# testBench.net
KiCad netlist of a schematic drawn in EAGLE
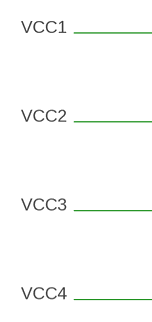
[diagram p0: schematic, sheet 1, part 1 of 2]
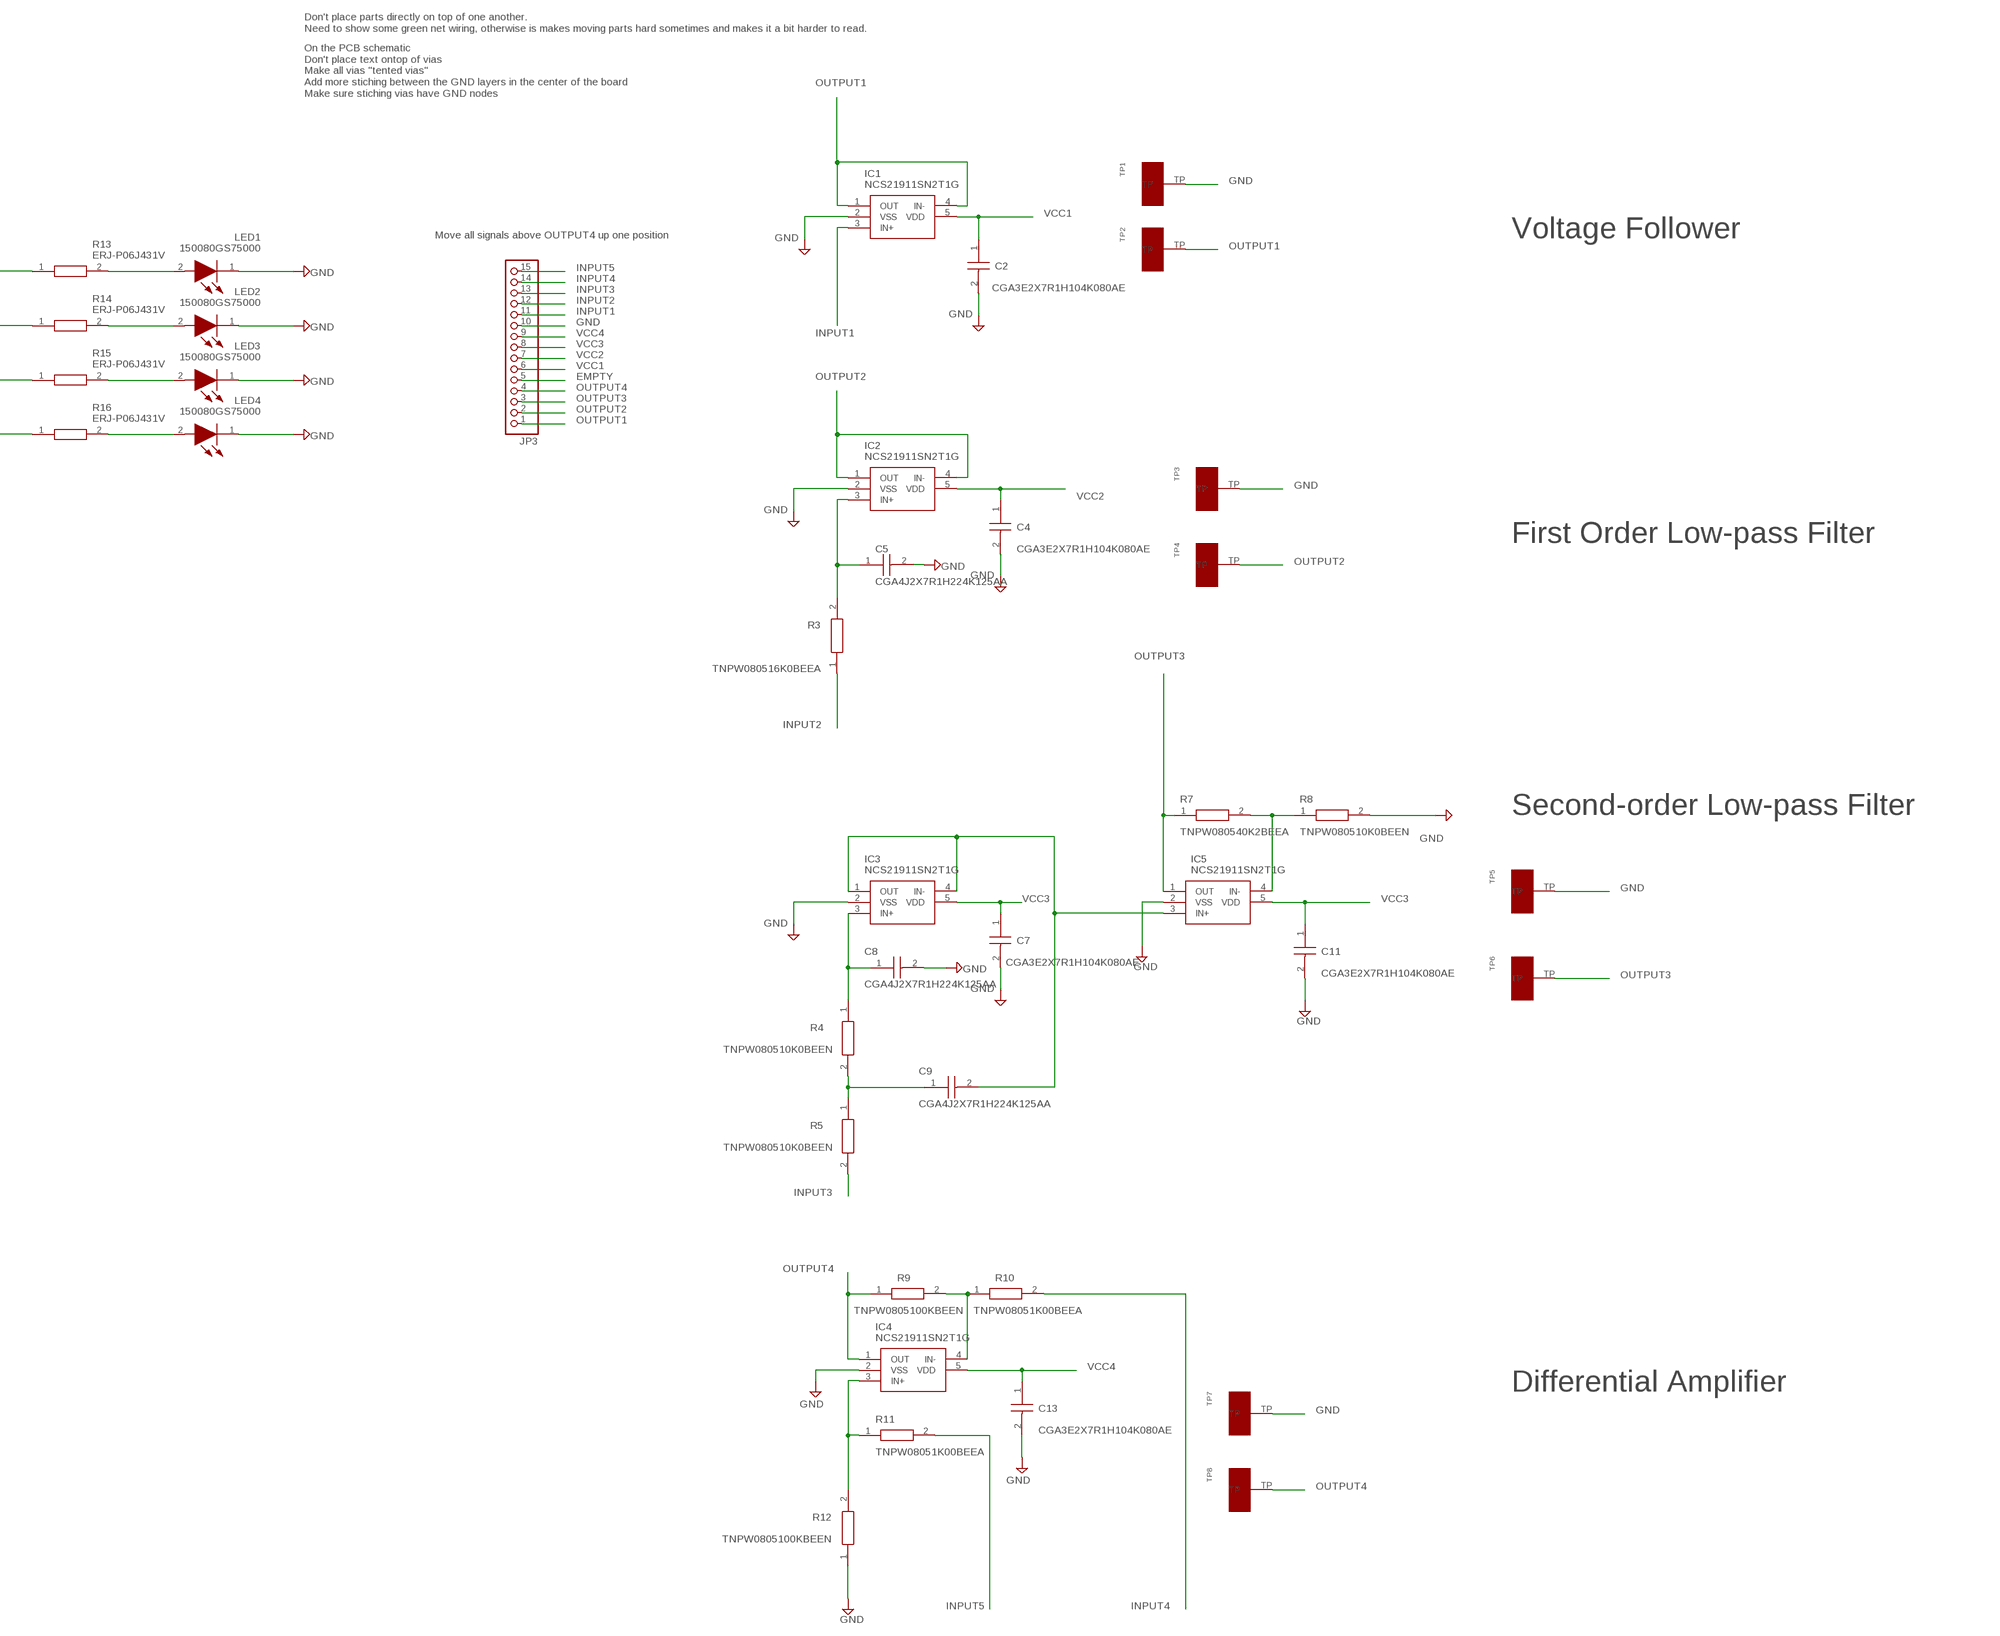
[diagram p1: schematic, sheet 1, part 2 of 2]

(export (version "E")
  (design (tool "Eeschema 10.0.6"))
  (components
    (comp (ref "C2")
      (value "CGA3E2X7R1H104K080AE")
      (footprint "eagle-import:CAPC1608X90N")
      (fields (field (name "MOUSER_PART_NUMBER") "810-CGA3E2X7R1H104KE"))
      (libsource (lib "eagle-import") (part "CGA3E2X7R1H104K080AE"))
    )
    (comp (ref "C4")
      (value "CGA3E2X7R1H104K080AE")
      (footprint "eagle-import:CAPC1608X90N")
      (fields (field (name "MOUSER_PART_NUMBER") "810-CGA3E2X7R1H104KE"))
      (libsource (lib "eagle-import") (part "CGA3E2X7R1H104K080AE"))
    )
    (comp (ref "C5")
      (value "CGA4J2X7R1H224K125AA")
      (footprint "eagle-import:CAPC2012X145N")
      (fields (field (name "MOUSER_PART_NUMBER") "810-CGA4J2X7R1H224K"))
      (libsource (lib "eagle-import") (part "CGA4J2X7R1H224K125AA"))
    )
    (comp (ref "C7")
      (value "CGA3E2X7R1H104K080AE")
      (footprint "eagle-import:CAPC1608X90N")
      (fields (field (name "MOUSER_PART_NUMBER") "810-CGA3E2X7R1H104KE"))
      (libsource (lib "eagle-import") (part "CGA3E2X7R1H104K080AE"))
    )
    (comp (ref "C8")
      (value "CGA4J2X7R1H224K125AA")
      (footprint "eagle-import:CAPC2012X145N")
      (fields (field (name "MOUSER_PART_NUMBER") "810-CGA4J2X7R1H224K"))
      (libsource (lib "eagle-import") (part "CGA4J2X7R1H224K125AA"))
    )
    (comp (ref "C9")
      (value "CGA4J2X7R1H224K125AA")
      (footprint "eagle-import:CAPC2012X145N")
      (fields (field (name "MOUSER_PART_NUMBER") "810-CGA4J2X7R1H224K"))
      (libsource (lib "eagle-import") (part "CGA4J2X7R1H224K125AA"))
    )
    (comp (ref "C11")
      (value "CGA3E2X7R1H104K080AE")
      (footprint "eagle-import:CAPC1608X90N")
      (fields (field (name "MOUSER_PART_NUMBER") "810-CGA3E2X7R1H104KE"))
      (libsource (lib "eagle-import") (part "CGA3E2X7R1H104K080AE"))
    )
    (comp (ref "C13")
      (value "CGA3E2X7R1H104K080AE")
      (footprint "eagle-import:CAPC1608X90N")
      (fields (field (name "MOUSER_PART_NUMBER") "810-CGA3E2X7R1H104KE"))
      (libsource (lib "eagle-import") (part "CGA3E2X7R1H104K080AE"))
    )
    (comp (ref "IC1")
      (value "NCS21911SN2T1G")
      (footprint "eagle-import:SOT95P275X110-5N")
      (fields (field (name "MOUSER_PART_NUMBER") "863-NCS21911SN2T1G"))
      (libsource (lib "eagle-import") (part "NCS21911SN2T1G"))
    )
    (comp (ref "IC2")
      (value "NCS21911SN2T1G")
      (footprint "eagle-import:SOT95P275X110-5N")
      (fields (field (name "MOUSER_PART_NUMBER") "863-NCS21911SN2T1G"))
      (libsource (lib "eagle-import") (part "NCS21911SN2T1G"))
    )
    (comp (ref "IC3")
      (value "NCS21911SN2T1G")
      (footprint "eagle-import:SOT95P275X110-5N")
      (fields (field (name "MOUSER_PART_NUMBER") "863-NCS21911SN2T1G"))
      (libsource (lib "eagle-import") (part "NCS21911SN2T1G"))
    )
    (comp (ref "IC4")
      (value "NCS21911SN2T1G")
      (footprint "eagle-import:SOT95P275X110-5N")
      (fields (field (name "MOUSER_PART_NUMBER") "863-NCS21911SN2T1G"))
      (libsource (lib "eagle-import") (part "NCS21911SN2T1G"))
    )
    (comp (ref "IC5")
      (value "NCS21911SN2T1G")
      (footprint "eagle-import:SOT95P275X110-5N")
      (fields (field (name "MOUSER_PART_NUMBER") "863-NCS21911SN2T1G"))
      (libsource (lib "eagle-import") (part "NCS21911SN2T1G"))
    )
    (comp (ref "JP3")
      (value "PINHD-1X15")
      (footprint "eagle-import:1X15")
      (libsource (lib "eagle-import") (part "PINHD-1X15"))
    )
    (comp (ref "LED1")
      (value "150080GS75000")
      (footprint "eagle-import:LEDM2012X80N")
      (fields (field (name "MOUSER_PART_NUMBER") "710-150080GS75000"))
      (libsource (lib "eagle-import") (part "150080GS75000"))
    )
    (comp (ref "LED2")
      (value "150080GS75000")
      (footprint "eagle-import:LEDM2012X80N")
      (fields (field (name "MOUSER_PART_NUMBER") "710-150080GS75000"))
      (libsource (lib "eagle-import") (part "150080GS75000"))
    )
    (comp (ref "LED3")
      (value "150080GS75000")
      (footprint "eagle-import:LEDM2012X80N")
      (fields (field (name "MOUSER_PART_NUMBER") "710-150080GS75000"))
      (libsource (lib "eagle-import") (part "150080GS75000"))
    )
    (comp (ref "LED4")
      (value "150080GS75000")
      (footprint "eagle-import:LEDM2012X80N")
      (fields (field (name "MOUSER_PART_NUMBER") "710-150080GS75000"))
      (libsource (lib "eagle-import") (part "150080GS75000"))
    )
    (comp (ref "R3")
      (value "TNPW080516K0BEEA")
      (footprint "eagle-import:RESC2013X65N")
      (fields
        (field (name "MANUFACTURER_PART_NUMBER") "TNPW080510K0BEEN")
        (field (name "MOUSER_PART_NUMBER") "71-TNPW080510K0BEEN")
      )
      (libsource (lib "eagle-import") (part "TNPW080510K0BEEN"))
    )
    (comp (ref "R4")
      (value "TNPW080510K0BEEN")
      (footprint "eagle-import:RESC2013X65N")
      (fields (field (name "MOUSER_PART_NUMBER") "71-TNPW080510K0BEEN"))
      (libsource (lib "eagle-import") (part "TNPW080510K0BEEN"))
    )
    (comp (ref "R5")
      (value "TNPW080510K0BEEN")
      (footprint "eagle-import:RESC2013X65N")
      (fields (field (name "MOUSER_PART_NUMBER") "71-TNPW080510K0BEEN"))
      (libsource (lib "eagle-import") (part "TNPW080510K0BEEN"))
    )
    (comp (ref "R7")
      (value "TNPW080540K2BEEA")
      (footprint "eagle-import:RESC2013X65N")
      (fields (field (name "MOUSER_PART_NUMBER") "71-TNPW080540K2BEEA"))
      (libsource (lib "eagle-import") (part "TNPW080540K2BEEA"))
    )
    (comp (ref "R8")
      (value "TNPW080510K0BEEN")
      (footprint "eagle-import:RESC2013X65N")
      (fields (field (name "MOUSER_PART_NUMBER") "71-TNPW080510K0BEEN"))
      (libsource (lib "eagle-import") (part "TNPW080510K0BEEN"))
    )
    (comp (ref "R9")
      (value "TNPW0805100KBEEN")
      (footprint "eagle-import:RESC2013X65N")
      (fields (field (name "MOUSER_PART_NUMBER") "71-TNPW0805100KBEEN"))
      (libsource (lib "eagle-import") (part "TNPW0805100KBEEN"))
    )
    (comp (ref "R10")
      (value "TNPW08051K00BEEA")
      (footprint "eagle-import:RESC2012X55N")
      (fields (field (name "MOUSER_PART_NUMBER") "71-TNPW08051K00BEEA"))
      (libsource (lib "eagle-import") (part "TNPW08051K00BEEA"))
    )
    (comp (ref "R11")
      (value "TNPW08051K00BEEA")
      (footprint "eagle-import:RESC2012X55N")
      (fields (field (name "MOUSER_PART_NUMBER") "71-TNPW08051K00BEEA"))
      (libsource (lib "eagle-import") (part "TNPW08051K00BEEA"))
    )
    (comp (ref "R12")
      (value "TNPW0805100KBEEN")
      (footprint "eagle-import:RESC2013X65N")
      (fields (field (name "MOUSER_PART_NUMBER") "71-TNPW0805100KBEEN"))
      (libsource (lib "eagle-import") (part "TNPW0805100KBEEN"))
    )
    (comp (ref "R13")
      (value "ERJ-P06J431V")
      (footprint "eagle-import:ERJP06_(0805)")
      (fields (field (name "MOUSER_PART_NUMBER") "667-ERJ-P06J431V"))
      (libsource (lib "eagle-import") (part "ERJ-P06J431V"))
    )
    (comp (ref "R14")
      (value "ERJ-P06J431V")
      (footprint "eagle-import:ERJP06_(0805)")
      (fields (field (name "MOUSER_PART_NUMBER") "667-ERJ-P06J431V"))
      (libsource (lib "eagle-import") (part "ERJ-P06J431V"))
    )
    (comp (ref "R15")
      (value "ERJ-P06J431V")
      (footprint "eagle-import:ERJP06_(0805)")
      (fields (field (name "MOUSER_PART_NUMBER") "667-ERJ-P06J431V"))
      (libsource (lib "eagle-import") (part "ERJ-P06J431V"))
    )
    (comp (ref "R16")
      (value "ERJ-P06J431V")
      (footprint "eagle-import:ERJP06_(0805)")
      (fields (field (name "MOUSER_PART_NUMBER") "667-ERJ-P06J431V"))
      (libsource (lib "eagle-import") (part "ERJ-P06J431V"))
    )
    (comp (ref "TP1")
      (value "S1751-46R")
      (footprint "eagle-import:1.85X3.45_MM")
      (fields (field (name "MOUSER_PART_NUMBER") "855-S1751-46R"))
      (libsource (lib "eagle-import") (part "S1751-46R"))
    )
    (comp (ref "TP2")
      (value "S1751-46R")
      (footprint "eagle-import:1.85X3.45_MM")
      (fields (field (name "MOUSER_PART_NUMBER") "855-S1751-46R"))
      (libsource (lib "eagle-import") (part "S1751-46R"))
    )
    (comp (ref "TP3")
      (value "S1751-46R")
      (footprint "eagle-import:1.85X3.45_MM")
      (fields (field (name "MOUSER_PART_NUMBER") "855-S1751-46R"))
      (libsource (lib "eagle-import") (part "S1751-46R"))
    )
    (comp (ref "TP4")
      (value "S1751-46R")
      (footprint "eagle-import:1.85X3.45_MM")
      (fields (field (name "MOUSER_PART_NUMBER") "855-S1751-46R"))
      (libsource (lib "eagle-import") (part "S1751-46R"))
    )
    (comp (ref "TP5")
      (value "S1751-46R")
      (footprint "eagle-import:1.85X3.45_MM")
      (fields (field (name "MOUSER_PART_NUMBER") "855-S1751-46R"))
      (libsource (lib "eagle-import") (part "S1751-46R"))
    )
    (comp (ref "TP6")
      (value "S1751-46R")
      (footprint "eagle-import:1.85X3.45_MM")
      (fields (field (name "MOUSER_PART_NUMBER") "855-S1751-46R"))
      (libsource (lib "eagle-import") (part "S1751-46R"))
    )
    (comp (ref "TP7")
      (value "S1751-46R")
      (footprint "eagle-import:1.85X3.45_MM")
      (fields (field (name "MOUSER_PART_NUMBER") "855-S1751-46R"))
      (libsource (lib "eagle-import") (part "S1751-46R"))
    )
    (comp (ref "TP8")
      (value "S1751-46R")
      (footprint "eagle-import:1.85X3.45_MM")
      (fields (field (name "MOUSER_PART_NUMBER") "855-S1751-46R"))
      (libsource (lib "eagle-import") (part "S1751-46R"))
    )
  )
  (nets
    (net (code "1") (name "/EMPTY") (class "Default")
      (node (ref "JP3") (pin "5") (pinfunction "5_5") (pintype "passive"))
    )
    (net (code "2") (name "/INPUT1") (class "Default")
      (node (ref "IC1") (pin "3") (pinfunction "IN+_3") (pintype "bidirectional"))
      (node (ref "JP3") (pin "11") (pinfunction "11_11") (pintype "passive"))
    )
    (net (code "3") (name "/INPUT2") (class "Default")
      (node (ref "JP3") (pin "12") (pinfunction "12_12") (pintype "passive"))
      (node (ref "R3") (pin "1") (pinfunction "1_1") (pintype "bidirectional"))
    )
    (net (code "4") (name "/INPUT3") (class "Default")
      (node (ref "JP3") (pin "13") (pinfunction "13_13") (pintype "passive"))
      (node (ref "R5") (pin "2") (pinfunction "2_2") (pintype "bidirectional"))
    )
    (net (code "5") (name "/INPUT4") (class "Default")
      (node (ref "JP3") (pin "14") (pinfunction "14_14") (pintype "passive"))
      (node (ref "R10") (pin "2") (pinfunction "2_2") (pintype "bidirectional"))
    )
    (net (code "6") (name "/INPUT5") (class "Default")
      (node (ref "JP3") (pin "15") (pinfunction "15_15") (pintype "passive"))
      (node (ref "R11") (pin "2") (pinfunction "2_2") (pintype "bidirectional"))
    )
    (net (code "7") (name "/OUTPUT1") (class "Default")
      (node (ref "IC1") (pin "1") (pinfunction "OUT_1") (pintype "bidirectional"))
      (node (ref "IC1") (pin "4") (pinfunction "IN-_4") (pintype "bidirectional"))
      (node (ref "JP3") (pin "1") (pinfunction "1_1") (pintype "passive"))
      (node (ref "TP2") (pin "TP") (pinfunction "TP_TP") (pintype "bidirectional"))
    )
    (net (code "8") (name "/OUTPUT2") (class "Default")
      (node (ref "IC2") (pin "1") (pinfunction "OUT_1") (pintype "bidirectional"))
      (node (ref "IC2") (pin "4") (pinfunction "IN-_4") (pintype "bidirectional"))
      (node (ref "JP3") (pin "2") (pinfunction "2_2") (pintype "passive"))
      (node (ref "TP4") (pin "TP") (pinfunction "TP_TP") (pintype "bidirectional"))
    )
    (net (code "9") (name "/OUTPUT3") (class "Default")
      (node (ref "IC5") (pin "1") (pinfunction "OUT_1") (pintype "bidirectional"))
      (node (ref "JP3") (pin "3") (pinfunction "3_3") (pintype "passive"))
      (node (ref "R7") (pin "1") (pinfunction "1_1") (pintype "bidirectional"))
      (node (ref "TP6") (pin "TP") (pinfunction "TP_TP") (pintype "bidirectional"))
    )
    (net (code "10") (name "/OUTPUT4") (class "Default")
      (node (ref "IC4") (pin "1") (pinfunction "OUT_1") (pintype "bidirectional"))
      (node (ref "JP3") (pin "4") (pinfunction "4_4") (pintype "passive"))
      (node (ref "R9") (pin "1") (pinfunction "1_1") (pintype "bidirectional"))
      (node (ref "TP8") (pin "TP") (pinfunction "TP_TP") (pintype "bidirectional"))
    )
    (net (code "11") (name "/VCC1") (class "Default")
      (node (ref "C2") (pin "1") (pinfunction "1_1") (pintype "bidirectional"))
      (node (ref "IC1") (pin "5") (pinfunction "VDD_5") (pintype "bidirectional"))
      (node (ref "JP3") (pin "6") (pinfunction "6_6") (pintype "passive"))
      (node (ref "R13") (pin "1") (pinfunction "1_1") (pintype "bidirectional"))
    )
    (net (code "12") (name "/VCC2") (class "Default")
      (node (ref "C4") (pin "1") (pinfunction "1_1") (pintype "bidirectional"))
      (node (ref "IC2") (pin "5") (pinfunction "VDD_5") (pintype "bidirectional"))
      (node (ref "JP3") (pin "7") (pinfunction "7_7") (pintype "passive"))
      (node (ref "R14") (pin "1") (pinfunction "1_1") (pintype "bidirectional"))
    )
    (net (code "13") (name "/VCC3") (class "Default")
      (node (ref "C11") (pin "1") (pinfunction "1_1") (pintype "bidirectional"))
      (node (ref "C7") (pin "1") (pinfunction "1_1") (pintype "bidirectional"))
      (node (ref "IC3") (pin "5") (pinfunction "VDD_5") (pintype "bidirectional"))
      (node (ref "IC5") (pin "5") (pinfunction "VDD_5") (pintype "bidirectional"))
      (node (ref "JP3") (pin "8") (pinfunction "8_8") (pintype "passive"))
      (node (ref "R15") (pin "1") (pinfunction "1_1") (pintype "bidirectional"))
    )
    (net (code "14") (name "/VCC4") (class "Default")
      (node (ref "C13") (pin "1") (pinfunction "1_1") (pintype "bidirectional"))
      (node (ref "IC4") (pin "5") (pinfunction "VDD_5") (pintype "bidirectional"))
      (node (ref "JP3") (pin "9") (pinfunction "9_9") (pintype "passive"))
      (node (ref "R16") (pin "1") (pinfunction "1_1") (pintype "bidirectional"))
    )
    (net (code "15") (name "GND") (class "Default")
      (node (ref "C11") (pin "2") (pinfunction "2_2") (pintype "bidirectional"))
      (node (ref "C13") (pin "2") (pinfunction "2_2") (pintype "bidirectional"))
      (node (ref "C2") (pin "2") (pinfunction "2_2") (pintype "bidirectional"))
      (node (ref "C4") (pin "2") (pinfunction "2_2") (pintype "bidirectional"))
      (node (ref "C5") (pin "2") (pinfunction "2_2") (pintype "bidirectional"))
      (node (ref "C7") (pin "2") (pinfunction "2_2") (pintype "bidirectional"))
      (node (ref "C8") (pin "2") (pinfunction "2_2") (pintype "bidirectional"))
      (node (ref "IC1") (pin "2") (pinfunction "VSS_2") (pintype "bidirectional"))
      (node (ref "IC2") (pin "2") (pinfunction "VSS_2") (pintype "bidirectional"))
      (node (ref "IC3") (pin "2") (pinfunction "VSS_2") (pintype "bidirectional"))
      (node (ref "IC4") (pin "2") (pinfunction "VSS_2") (pintype "bidirectional"))
      (node (ref "IC5") (pin "2") (pinfunction "VSS_2") (pintype "bidirectional"))
      (node (ref "JP3") (pin "10") (pinfunction "10_10") (pintype "passive"))
      (node (ref "LED1") (pin "1") (pinfunction "K_1") (pintype "bidirectional"))
      (node (ref "LED2") (pin "1") (pinfunction "K_1") (pintype "bidirectional"))
      (node (ref "LED3") (pin "1") (pinfunction "K_1") (pintype "bidirectional"))
      (node (ref "LED4") (pin "1") (pinfunction "K_1") (pintype "bidirectional"))
      (node (ref "R12") (pin "1") (pinfunction "1_1") (pintype "bidirectional"))
      (node (ref "R8") (pin "2") (pinfunction "2_2") (pintype "bidirectional"))
      (node (ref "TP1") (pin "TP") (pinfunction "TP_TP") (pintype "bidirectional"))
      (node (ref "TP3") (pin "TP") (pinfunction "TP_TP") (pintype "bidirectional"))
      (node (ref "TP5") (pin "TP") (pinfunction "TP_TP") (pintype "bidirectional"))
      (node (ref "TP7") (pin "TP") (pinfunction "TP_TP") (pintype "bidirectional"))
    )
    (net (code "16") (name "Net-(C9-Pad1)") (class "Default")
      (node (ref "C9") (pin "1") (pinfunction "1_1") (pintype "bidirectional"))
      (node (ref "R4") (pin "2") (pinfunction "2_2") (pintype "bidirectional"))
      (node (ref "R5") (pin "1") (pinfunction "1_1") (pintype "bidirectional"))
    )
    (net (code "17") (name "Net-(IC2-IN+)") (class "Default")
      (node (ref "C5") (pin "1") (pinfunction "1_1") (pintype "bidirectional"))
      (node (ref "IC2") (pin "3") (pinfunction "IN+_3") (pintype "bidirectional"))
      (node (ref "R3") (pin "2") (pinfunction "2_2") (pintype "bidirectional"))
    )
    (net (code "18") (name "Net-(IC3-IN+)") (class "Default")
      (node (ref "C8") (pin "1") (pinfunction "1_1") (pintype "bidirectional"))
      (node (ref "IC3") (pin "3") (pinfunction "IN+_3") (pintype "bidirectional"))
      (node (ref "R4") (pin "1") (pinfunction "1_1") (pintype "bidirectional"))
    )
    (net (code "19") (name "Net-(IC3-IN-)") (class "Default")
      (node (ref "C9") (pin "2") (pinfunction "2_2") (pintype "bidirectional"))
      (node (ref "IC3") (pin "1") (pinfunction "OUT_1") (pintype "bidirectional"))
      (node (ref "IC3") (pin "4") (pinfunction "IN-_4") (pintype "bidirectional"))
      (node (ref "IC5") (pin "3") (pinfunction "IN+_3") (pintype "bidirectional"))
    )
    (net (code "20") (name "Net-(IC4-IN+)") (class "Default")
      (node (ref "IC4") (pin "3") (pinfunction "IN+_3") (pintype "bidirectional"))
      (node (ref "R11") (pin "1") (pinfunction "1_1") (pintype "bidirectional"))
      (node (ref "R12") (pin "2") (pinfunction "2_2") (pintype "bidirectional"))
    )
    (net (code "21") (name "Net-(IC4-IN-)") (class "Default")
      (node (ref "IC4") (pin "4") (pinfunction "IN-_4") (pintype "bidirectional"))
      (node (ref "R10") (pin "1") (pinfunction "1_1") (pintype "bidirectional"))
      (node (ref "R9") (pin "2") (pinfunction "2_2") (pintype "bidirectional"))
    )
    (net (code "22") (name "Net-(IC5-IN-)") (class "Default")
      (node (ref "IC5") (pin "4") (pinfunction "IN-_4") (pintype "bidirectional"))
      (node (ref "R7") (pin "2") (pinfunction "2_2") (pintype "bidirectional"))
      (node (ref "R8") (pin "1") (pinfunction "1_1") (pintype "bidirectional"))
    )
    (net (code "23") (name "Net-(LED1-A)") (class "Default")
      (node (ref "LED1") (pin "2") (pinfunction "A_2") (pintype "bidirectional"))
      (node (ref "R13") (pin "2") (pinfunction "2_2") (pintype "bidirectional"))
    )
    (net (code "24") (name "Net-(LED2-A)") (class "Default")
      (node (ref "LED2") (pin "2") (pinfunction "A_2") (pintype "bidirectional"))
      (node (ref "R14") (pin "2") (pinfunction "2_2") (pintype "bidirectional"))
    )
    (net (code "25") (name "Net-(LED3-A)") (class "Default")
      (node (ref "LED3") (pin "2") (pinfunction "A_2") (pintype "bidirectional"))
      (node (ref "R15") (pin "2") (pinfunction "2_2") (pintype "bidirectional"))
    )
    (net (code "26") (name "Net-(LED4-A)") (class "Default")
      (node (ref "LED4") (pin "2") (pinfunction "A_2") (pintype "bidirectional"))
      (node (ref "R16") (pin "2") (pinfunction "2_2") (pintype "bidirectional"))
    )
  )
)
